# M115.net
KiCad netlist of a schematic drawn in EAGLE
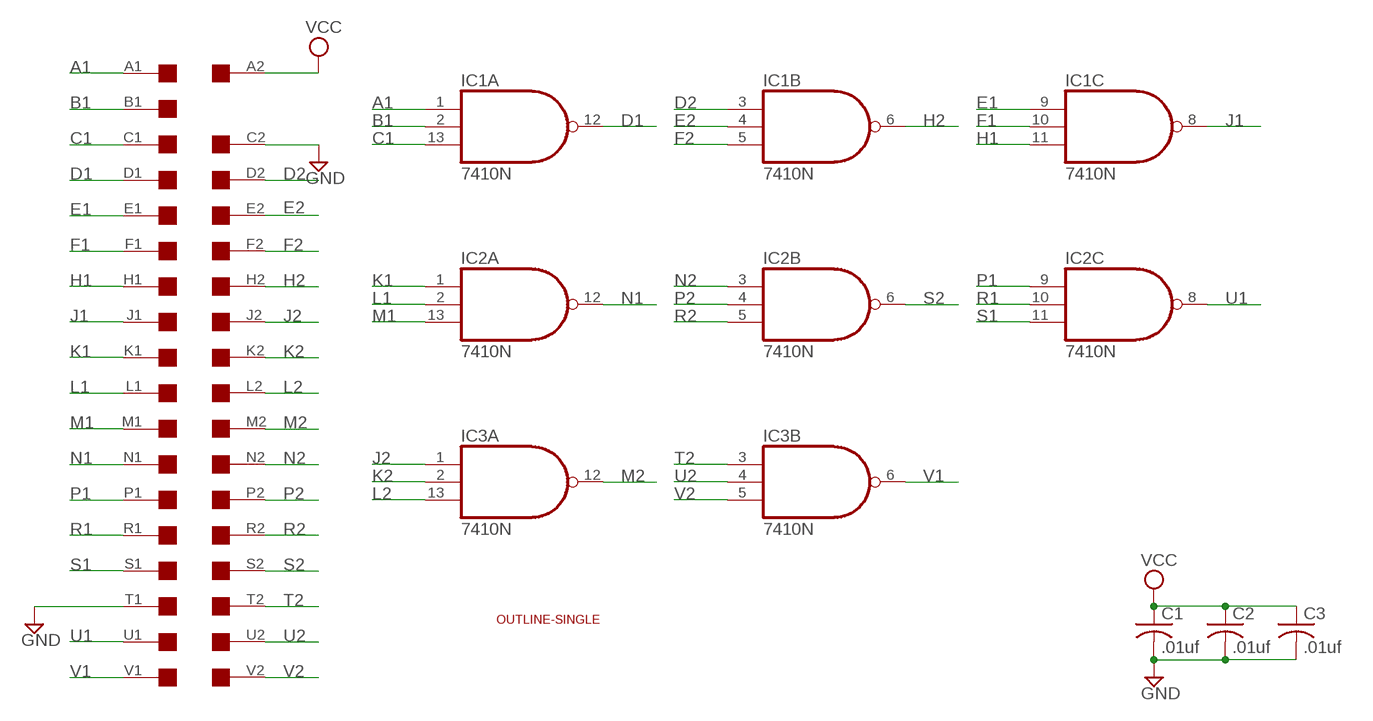
[diagram p0: schematic, sheet 1]

(export (version "E")
  (design (tool "Eeschema 10.0.6"))
  (components
    (comp (ref "C1")
      (value ".01uf")
      (footprint "eagle-import:C050-025X075")
      (libsource (lib "eagle-import") (part "C-US050-025X075"))
    )
    (comp (ref "C2")
      (value ".01uf")
      (footprint "eagle-import:C050-025X075")
      (libsource (lib "eagle-import") (part "C-US050-025X075"))
    )
    (comp (ref "C3")
      (value ".01uf")
      (footprint "eagle-import:C050-025X075")
      (libsource (lib "eagle-import") (part "C-US050-025X075"))
    )
    (comp (ref "IC1")
      (value "7410N")
      (footprint "eagle-import:DIL14")
      (libsource (lib "eagle-import") (part "7410N"))
    )
    (comp (ref "IC2")
      (value "7410N")
      (footprint "eagle-import:DIL14")
      (libsource (lib "eagle-import") (part "7410N"))
    )
    (comp (ref "IC3")
      (value "7410N")
      (footprint "eagle-import:DIL14")
      (libsource (lib "eagle-import") (part "7410N"))
    )
    (comp (ref "U$1")
      (value "SINGLE")
      (footprint "eagle-import:EDGE-CON2")
      (libsource (lib "eagle-import") (part "SINGLE"))
    )
    (comp (ref "U$4")
      (value "OUTLINE-SINGLE")
      (footprint "eagle-import:SINGLE")
      (libsource (lib "eagle-import") (part "OUTLINE-SINGLE"))
    )
  )
  (nets
    (net (code "1") (name "/A1") (class "Default")
      (node (ref "IC1") (pin "1") (pinfunction "I0_1") (pintype "input"))
      (node (ref "U$1") (pin "A1") (pinfunction "1_A1") (pintype "bidirectional"))
    )
    (net (code "2") (name "/B1") (class "Default")
      (node (ref "IC1") (pin "2") (pinfunction "I1_2") (pintype "input"))
      (node (ref "U$1") (pin "B1") (pinfunction "1_B1") (pintype "bidirectional"))
    )
    (net (code "3") (name "/C1") (class "Default")
      (node (ref "IC1") (pin "13") (pinfunction "I2_13") (pintype "input"))
      (node (ref "U$1") (pin "C1") (pinfunction "1_C1") (pintype "bidirectional"))
    )
    (net (code "4") (name "/D1") (class "Default")
      (node (ref "IC1") (pin "12") (pinfunction "O_12") (pintype "output"))
      (node (ref "U$1") (pin "D1") (pinfunction "1_D1") (pintype "bidirectional"))
    )
    (net (code "5") (name "/D2") (class "Default")
      (node (ref "IC1") (pin "3") (pinfunction "I0_3") (pintype "input"))
      (node (ref "U$1") (pin "D2") (pinfunction "1_D2") (pintype "bidirectional"))
    )
    (net (code "6") (name "/E1") (class "Default")
      (node (ref "IC1") (pin "9") (pinfunction "I0_9") (pintype "input"))
      (node (ref "U$1") (pin "E1") (pinfunction "1_E1") (pintype "bidirectional"))
    )
    (net (code "7") (name "/E2") (class "Default")
      (node (ref "IC1") (pin "4") (pinfunction "I1_4") (pintype "input"))
      (node (ref "U$1") (pin "E2") (pinfunction "1_E2") (pintype "bidirectional"))
    )
    (net (code "8") (name "/F1") (class "Default")
      (node (ref "IC1") (pin "10") (pinfunction "I1_10") (pintype "input"))
      (node (ref "U$1") (pin "F1") (pinfunction "1_F1") (pintype "bidirectional"))
    )
    (net (code "9") (name "/F2") (class "Default")
      (node (ref "IC1") (pin "5") (pinfunction "I2_5") (pintype "input"))
      (node (ref "U$1") (pin "F2") (pinfunction "1_F2") (pintype "bidirectional"))
    )
    (net (code "10") (name "/H1") (class "Default")
      (node (ref "IC1") (pin "11") (pinfunction "I2_11") (pintype "input"))
      (node (ref "U$1") (pin "H1") (pinfunction "1_H1") (pintype "bidirectional"))
    )
    (net (code "11") (name "/H2") (class "Default")
      (node (ref "IC1") (pin "6") (pinfunction "O_6") (pintype "output"))
      (node (ref "U$1") (pin "H2") (pinfunction "1_H2") (pintype "bidirectional"))
    )
    (net (code "12") (name "/J1") (class "Default")
      (node (ref "IC1") (pin "8") (pinfunction "O_8") (pintype "output"))
      (node (ref "U$1") (pin "J1") (pinfunction "1_J1") (pintype "bidirectional"))
    )
    (net (code "13") (name "/J2") (class "Default")
      (node (ref "IC3") (pin "1") (pinfunction "I0_1") (pintype "input"))
      (node (ref "U$1") (pin "J2") (pinfunction "1_J2") (pintype "bidirectional"))
    )
    (net (code "14") (name "/K1") (class "Default")
      (node (ref "IC2") (pin "1") (pinfunction "I0_1") (pintype "input"))
      (node (ref "U$1") (pin "K1") (pinfunction "1_K1") (pintype "bidirectional"))
    )
    (net (code "15") (name "/K2") (class "Default")
      (node (ref "IC3") (pin "2") (pinfunction "I1_2") (pintype "input"))
      (node (ref "U$1") (pin "K2") (pinfunction "1_K2") (pintype "bidirectional"))
    )
    (net (code "16") (name "/L1") (class "Default")
      (node (ref "IC2") (pin "2") (pinfunction "I1_2") (pintype "input"))
      (node (ref "U$1") (pin "L1") (pinfunction "1_L1") (pintype "bidirectional"))
    )
    (net (code "17") (name "/L2") (class "Default")
      (node (ref "IC3") (pin "13") (pinfunction "I2_13") (pintype "input"))
      (node (ref "U$1") (pin "L2") (pinfunction "1_L2") (pintype "bidirectional"))
    )
    (net (code "18") (name "/M1") (class "Default")
      (node (ref "IC2") (pin "13") (pinfunction "I2_13") (pintype "input"))
      (node (ref "U$1") (pin "M1") (pinfunction "1_M1") (pintype "bidirectional"))
    )
    (net (code "19") (name "/M2") (class "Default")
      (node (ref "IC3") (pin "12") (pinfunction "O_12") (pintype "output"))
      (node (ref "U$1") (pin "M2") (pinfunction "1_M2") (pintype "bidirectional"))
    )
    (net (code "20") (name "/N1") (class "Default")
      (node (ref "IC2") (pin "12") (pinfunction "O_12") (pintype "output"))
      (node (ref "U$1") (pin "N1") (pinfunction "1_N1") (pintype "bidirectional"))
    )
    (net (code "21") (name "/N2") (class "Default")
      (node (ref "IC2") (pin "3") (pinfunction "I0_3") (pintype "input"))
      (node (ref "U$1") (pin "N2") (pinfunction "1_N2") (pintype "bidirectional"))
    )
    (net (code "22") (name "/P1") (class "Default")
      (node (ref "IC2") (pin "9") (pinfunction "I0_9") (pintype "input"))
      (node (ref "U$1") (pin "P1") (pinfunction "1_P1") (pintype "bidirectional"))
    )
    (net (code "23") (name "/P2") (class "Default")
      (node (ref "IC2") (pin "4") (pinfunction "I1_4") (pintype "input"))
      (node (ref "U$1") (pin "P2") (pinfunction "1_P2") (pintype "bidirectional"))
    )
    (net (code "24") (name "/R1") (class "Default")
      (node (ref "IC2") (pin "10") (pinfunction "I1_10") (pintype "input"))
      (node (ref "U$1") (pin "R1") (pinfunction "1_R1") (pintype "bidirectional"))
    )
    (net (code "25") (name "/R2") (class "Default")
      (node (ref "IC2") (pin "5") (pinfunction "I2_5") (pintype "input"))
      (node (ref "U$1") (pin "R2") (pinfunction "1_R2") (pintype "bidirectional"))
    )
    (net (code "26") (name "/S1") (class "Default")
      (node (ref "IC2") (pin "11") (pinfunction "I2_11") (pintype "input"))
      (node (ref "U$1") (pin "S1") (pinfunction "1_S1") (pintype "bidirectional"))
    )
    (net (code "27") (name "/S2") (class "Default")
      (node (ref "IC2") (pin "6") (pinfunction "O_6") (pintype "output"))
      (node (ref "U$1") (pin "S2") (pinfunction "1_S2") (pintype "bidirectional"))
    )
    (net (code "28") (name "/T2") (class "Default")
      (node (ref "IC3") (pin "3") (pinfunction "I0_3") (pintype "input"))
      (node (ref "U$1") (pin "T2") (pinfunction "1_T2") (pintype "bidirectional"))
    )
    (net (code "29") (name "/U1") (class "Default")
      (node (ref "IC2") (pin "8") (pinfunction "O_8") (pintype "output"))
      (node (ref "U$1") (pin "U1") (pinfunction "1_U1") (pintype "bidirectional"))
    )
    (net (code "30") (name "/U2") (class "Default")
      (node (ref "IC3") (pin "4") (pinfunction "I1_4") (pintype "input"))
      (node (ref "U$1") (pin "U2") (pinfunction "1_U2") (pintype "bidirectional"))
    )
    (net (code "31") (name "/V1") (class "Default")
      (node (ref "IC3") (pin "6") (pinfunction "O_6") (pintype "output"))
      (node (ref "U$1") (pin "V1") (pinfunction "1_V1") (pintype "bidirectional"))
    )
    (net (code "32") (name "/V2") (class "Default")
      (node (ref "IC3") (pin "5") (pinfunction "I2_5") (pintype "input"))
      (node (ref "U$1") (pin "V2") (pinfunction "1_V2") (pintype "bidirectional"))
    )
    (net (code "33") (name "GND") (class "Default")
      (node (ref "C1") (pin "2") (pinfunction "2_2") (pintype "passive"))
      (node (ref "C2") (pin "2") (pinfunction "2_2") (pintype "passive"))
      (node (ref "C3") (pin "2") (pinfunction "2_2") (pintype "passive"))
      (node (ref "U$1") (pin "C2") (pinfunction "1_C2") (pintype "bidirectional"))
      (node (ref "U$1") (pin "T1") (pinfunction "1_T1") (pintype "bidirectional"))
    )
    (net (code "34") (name "VCC") (class "Default")
      (node (ref "C1") (pin "1") (pinfunction "1_1") (pintype "passive"))
      (node (ref "C2") (pin "1") (pinfunction "1_1") (pintype "passive"))
      (node (ref "C3") (pin "1") (pinfunction "1_1") (pintype "passive"))
      (node (ref "U$1") (pin "A2") (pinfunction "1_A2") (pintype "bidirectional"))
    )
  )
)
